# usb-current-limiter.net
KiCad netlist of a schematic drawn in EAGLE
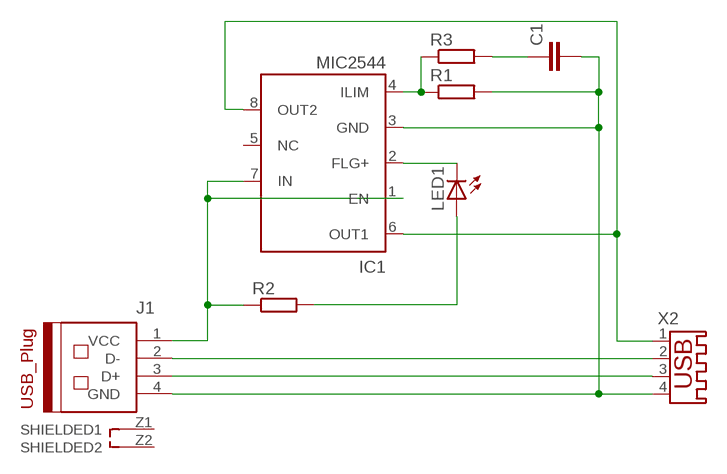
[diagram p0: schematic, sheet 1]

(export (version "E")
  (design (tool "Eeschema 10.0.6"))
  (components
    (comp (ref "C1")
      (value "C-EUC0805K")
      (footprint "eagle-import:C0805K")
      (libsource (lib "eagle-import") (part "C-EUC0805K"))
    )
    (comp (ref "IC1")
      (value "MIC2544")
      (footprint "eagle-import:SO-08")
      (fields (field (name "MF") "MICROCHIP") (field (name "MPN") "MIC2544-50-E/SN"))
      (libsource (lib "eagle-import") (part "MCP355SN0-50"))
    )
    (comp (ref "J1")
      (value "629004113921")
      (footprint "eagle-import:629004113921")
      (libsource (lib "eagle-import") (part "629004113921"))
    )
    (comp (ref "LED1")
      (value "LEDCHIPLED_0805")
      (footprint "eagle-import:CHIPLED_0805")
      (libsource (lib "eagle-import") (part "LEDCHIPLED_0805"))
    )
    (comp (ref "R1")
      (value "R-EU_M0805")
      (footprint "eagle-import:M0805")
      (libsource (lib "eagle-import") (part "R-EU_M0805"))
    )
    (comp (ref "R2")
      (value "R-EU_M0805")
      (footprint "eagle-import:M0805")
      (libsource (lib "eagle-import") (part "R-EU_M0805"))
    )
    (comp (ref "R3")
      (value "R-EU_M0805")
      (footprint "eagle-import:M0805")
      (libsource (lib "eagle-import") (part "R-EU_M0805"))
    )
    (comp (ref "X2")
      (value "USB-A003")
      (footprint "eagle-import:USB-A003")
      (libsource (lib "eagle-import") (part "USB-A003"))
    )
  )
  (nets
    (net (code "1") (name "Net-(C1-Pad1)") (class "Default")
      (node (ref "C1") (pin "1") (pinfunction "1_1") (pintype "passive"))
      (node (ref "R3") (pin "2") (pinfunction "2_2") (pintype "passive"))
    )
    (net (code "2") (name "Net-(IC1-EN)") (class "Default")
      (node (ref "IC1") (pin "1") (pinfunction "EN_1") (pintype "input"))
      (node (ref "IC1") (pin "7") (pinfunction "IN_7") (pintype "input"))
      (node (ref "J1") (pin "1") (pinfunction "VCC_1") (pintype "passive"))
      (node (ref "R2") (pin "1") (pinfunction "1_1") (pintype "passive"))
    )
    (net (code "3") (name "Net-(IC1-FLG+)") (class "Default")
      (node (ref "IC1") (pin "2") (pinfunction "FLG+_2") (pintype "input"))
      (node (ref "LED1") (pin "C") (pinfunction "C_C") (pintype "passive"))
    )
    (net (code "4") (name "Net-(IC1-GND)") (class "Default")
      (node (ref "C1") (pin "2") (pinfunction "2_2") (pintype "passive"))
      (node (ref "IC1") (pin "3") (pinfunction "GND_3") (pintype "input"))
      (node (ref "J1") (pin "4") (pinfunction "GND_4") (pintype "passive"))
      (node (ref "R1") (pin "2") (pinfunction "2_2") (pintype "passive"))
      (node (ref "X2") (pin "4") (pinfunction "4_4") (pintype "passive"))
    )
    (net (code "5") (name "Net-(IC1-ILIM)") (class "Default")
      (node (ref "IC1") (pin "4") (pinfunction "ILIM_4") (pintype "power_in"))
      (node (ref "R1") (pin "1") (pinfunction "1_1") (pintype "passive"))
      (node (ref "R3") (pin "1") (pinfunction "1_1") (pintype "passive"))
    )
    (net (code "6") (name "Net-(IC1-OUT1)") (class "Default")
      (node (ref "IC1") (pin "6") (pinfunction "OUT1_6") (pintype "power_in"))
      (node (ref "IC1") (pin "8") (pinfunction "OUT2_8") (pintype "output"))
      (node (ref "X2") (pin "1") (pinfunction "1_1") (pintype "passive"))
    )
    (net (code "7") (name "Net-(J1-D+)") (class "Default")
      (node (ref "J1") (pin "3") (pinfunction "D+_3") (pintype "passive"))
      (node (ref "X2") (pin "3") (pinfunction "3_3") (pintype "passive"))
    )
    (net (code "8") (name "Net-(J1-D-)") (class "Default")
      (node (ref "J1") (pin "2") (pinfunction "D-_2") (pintype "passive"))
      (node (ref "X2") (pin "2") (pinfunction "2_2") (pintype "passive"))
    )
    (net (code "9") (name "Net-(LED1-PadA)") (class "Default")
      (node (ref "LED1") (pin "A") (pinfunction "A_A") (pintype "passive"))
      (node (ref "R2") (pin "2") (pinfunction "2_2") (pintype "passive"))
    )
    (net (code "10") (name "unconnected-(IC1-NC-Pad5)") (class "Default")
      (node (ref "IC1") (pin "5") (pinfunction "NC_5") (pintype "input"))
    )
    (net (code "11") (name "unconnected-(J1-SHIELDED1-PadZ1)") (class "Default")
      (node (ref "J1") (pin "Z1") (pinfunction "SHIELDED1_Z1") (pintype "bidirectional"))
    )
    (net (code "12") (name "unconnected-(J1-SHIELDED2-PadZ2)") (class "Default")
      (node (ref "J1") (pin "Z2") (pinfunction "SHIELDED2_Z2") (pintype "bidirectional"))
    )
  )
)
